# Schematic.net
KiCad netlist of a schematic drawn in EAGLE
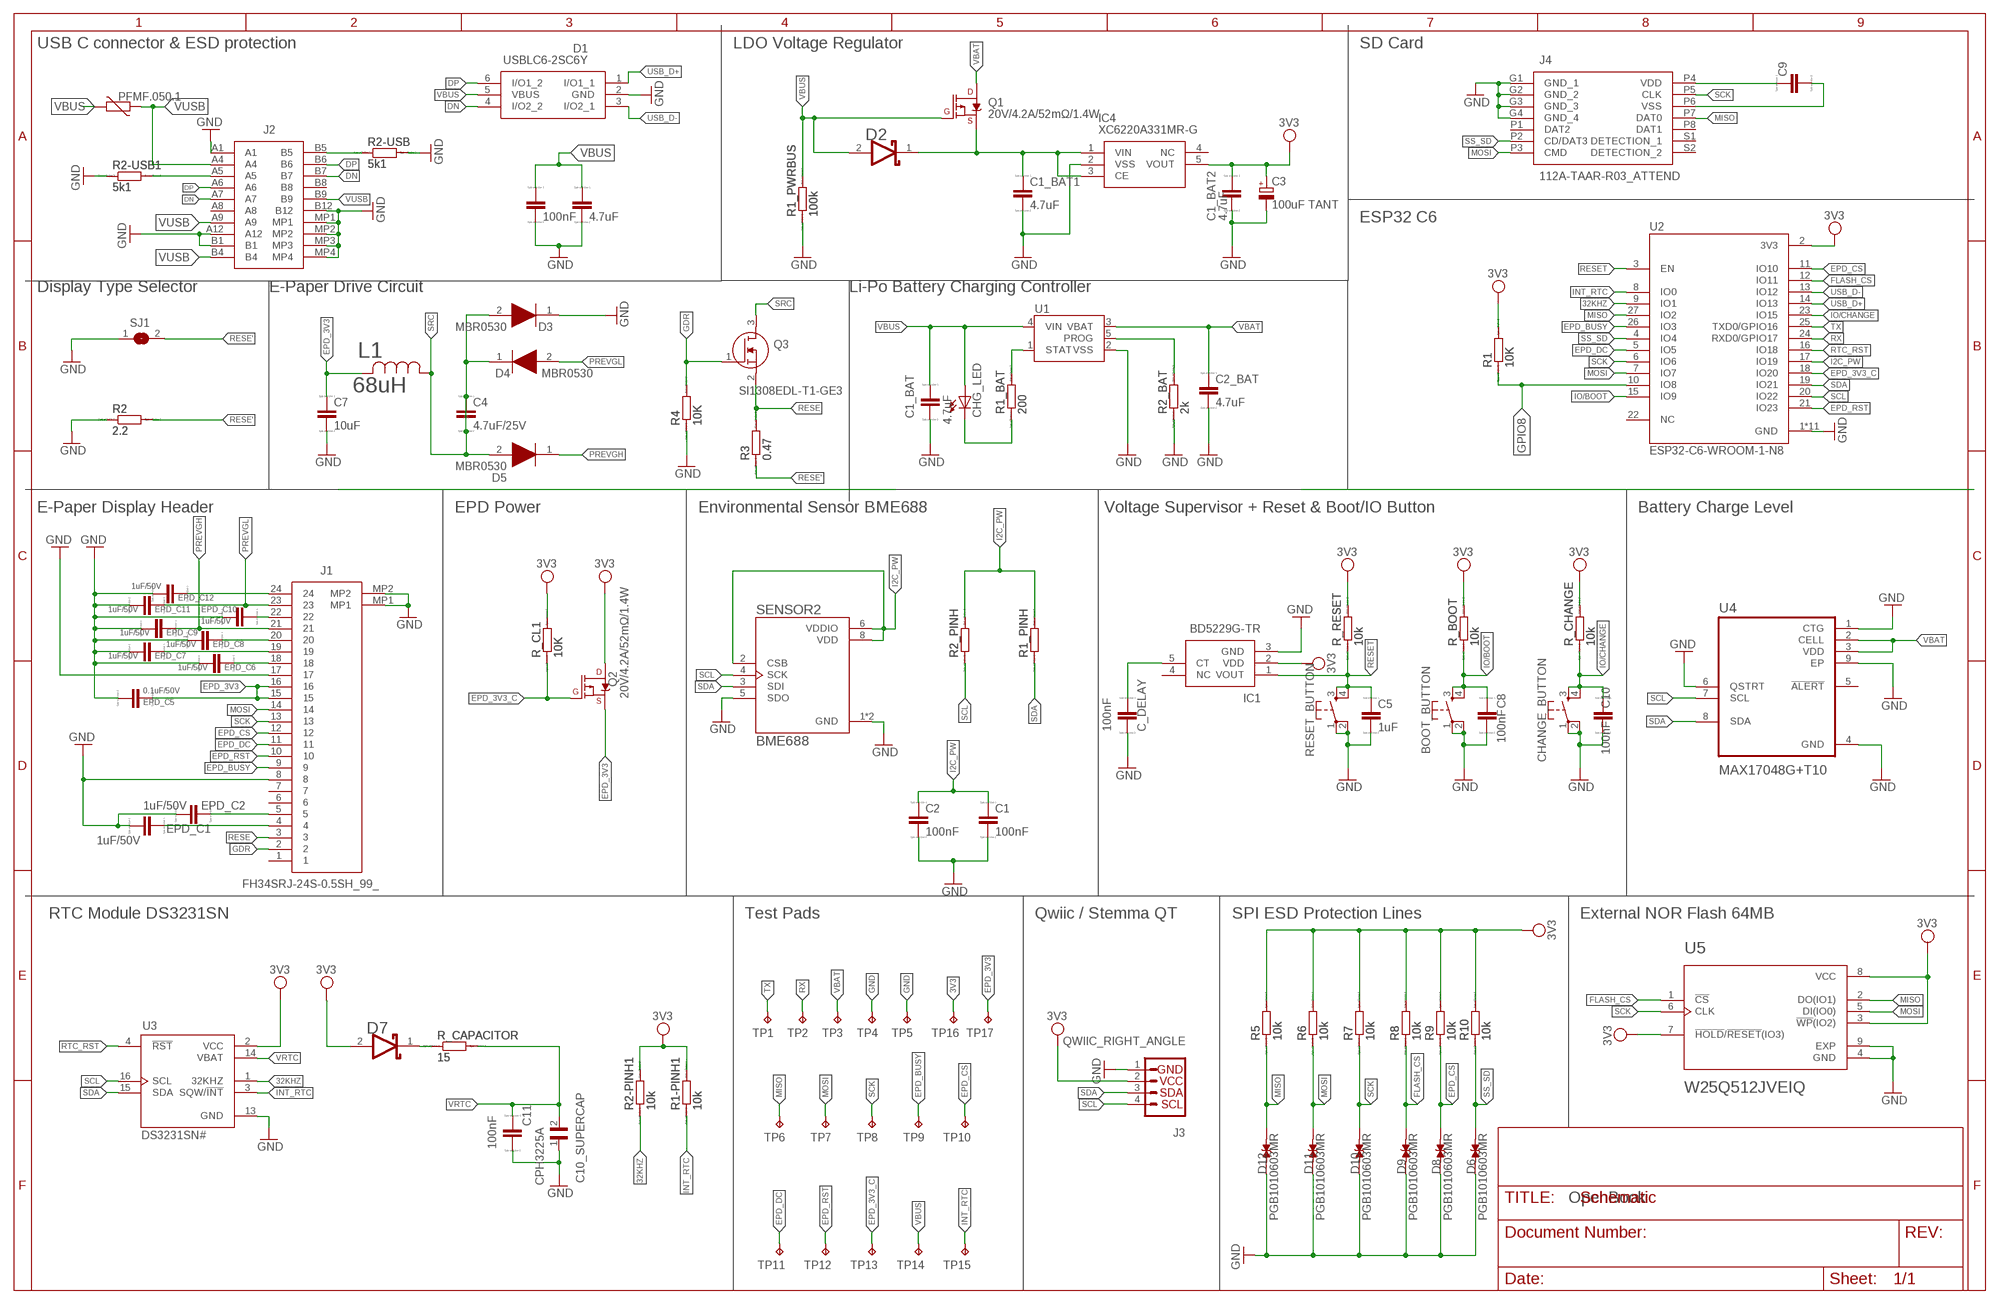
[diagram p0: schematic, sheet 1]

(export (version "E")
  (design (tool "Eeschema 10.0.6"))
  (components
    (comp (ref "BOOT_BUTTON")
      (value "BUTTON_CUSYOMV1")
      (footprint "eagle-import:MYBUTTON")
      (libsource (lib "eagle-import") (part "BUTTON_CUSYOMV1"))
    )
    (comp (ref "C1")
      (value "100nF")
      (footprint "eagle-import:ESP32_WROVER_EAGLE-LTSPICE_C0402")
      (libsource (lib "eagle-import") (part "ESP32_WROVER_EAGLE-LTSPICE_CC0402"))
    )
    (comp (ref "C1_BAT")
      (value "4.7uF")
      (footprint "eagle-import:EAGLE-LTSPICE_C0402")
      (libsource (lib "eagle-import") (part "EAGLE-LTSPICE_CC0402"))
    )
    (comp (ref "C1_BAT1")
      (value "4.7uF")
      (footprint "eagle-import:EAGLE-LTSPICE_C0402")
      (libsource (lib "eagle-import") (part "EAGLE-LTSPICE_CC0402"))
    )
    (comp (ref "C1_BAT2")
      (value "4.7uF")
      (footprint "eagle-import:EAGLE-LTSPICE_C0402")
      (libsource (lib "eagle-import") (part "EAGLE-LTSPICE_CC0402"))
    )
    (comp (ref "C2")
      (value "100nF")
      (footprint "eagle-import:ESP32_WROVER_EAGLE-LTSPICE_C0402")
      (libsource (lib "eagle-import") (part "ESP32_WROVER_EAGLE-LTSPICE_CC0402"))
    )
    (comp (ref "C2_BAT")
      (value "4.7uF")
      (footprint "eagle-import:EAGLE-LTSPICE_C0402")
      (libsource (lib "eagle-import") (part "EAGLE-LTSPICE_CC0402"))
    )
    (comp (ref "C3")
      (value "100uF TANT")
      (footprint "eagle-import:RCL_CT3528")
      (libsource (lib "eagle-import") (part "RCL_CPOL-EUCT3528"))
    )
    (comp (ref "C4")
      (value "4.7uF/25V")
      (footprint "eagle-import:EAGLE-LTSPICE_C0402")
      (libsource (lib "eagle-import") (part "EAGLE-LTSPICE_CC0402"))
    )
    (comp (ref "C4_USB")
      (value "100nF")
      (footprint "eagle-import:EAGLE-LTSPICE_C0402")
      (libsource (lib "eagle-import") (part "EAGLE-LTSPICE_CC0402"))
    )
    (comp (ref "C5")
      (value "1uF")
      (footprint "eagle-import:EAGLE-LTSPICE_C0402")
      (libsource (lib "eagle-import") (part "EAGLE-LTSPICE_CC0402"))
    )
    (comp (ref "C5_USB")
      (value "4.7uF")
      (footprint "eagle-import:EAGLE-LTSPICE_C0402")
      (libsource (lib "eagle-import") (part "EAGLE-LTSPICE_CC0402"))
    )
    (comp (ref "C7")
      (value "10uF")
      (footprint "eagle-import:EAGLE-LTSPICE_C0402")
      (libsource (lib "eagle-import") (part "EAGLE-LTSPICE_CC0402"))
    )
    (comp (ref "C8")
      (value "100nF")
      (footprint "eagle-import:EAGLE-LTSPICE_C0402")
      (libsource (lib "eagle-import") (part "EAGLE-LTSPICE_CC0402"))
    )
    (comp (ref "C9")
      (value "EAGLE-LTSPICE_CC0402")
      (footprint "eagle-import:EAGLE-LTSPICE_C0402")
      (libsource (lib "eagle-import") (part "EAGLE-LTSPICE_CC0402"))
    )
    (comp (ref "C10")
      (value "100nF")
      (footprint "eagle-import:EAGLE-LTSPICE_C0402")
      (libsource (lib "eagle-import") (part "EAGLE-LTSPICE_CC0402"))
    )
    (comp (ref "C10_SUPERCAP")
      (value "CPH3225A")
      (footprint "eagle-import:CAPCP3225X100N")
      (fields (field (name "MF") "Seiko Instruments"))
      (libsource (lib "eagle-import") (part "CPH3225A"))
    )
    (comp (ref "C11")
      (value "100nF")
      (footprint "eagle-import:EAGLE-LTSPICE_C0402")
      (libsource (lib "eagle-import") (part "EAGLE-LTSPICE_CC0402"))
    )
    (comp (ref "CHANGE_BUTTON")
      (value "BUTTON_CUSYOMV1")
      (footprint "eagle-import:MYBUTTON")
      (libsource (lib "eagle-import") (part "BUTTON_CUSYOMV1"))
    )
    (comp (ref "CHG_LED")
      (value "ADAFRUIT_LEDCHIP-LED0603")
      (footprint "eagle-import:ADAFRUIT_CHIP-LED0603")
      (libsource (lib "eagle-import") (part "ADAFRUIT_LEDCHIP-LED0603"))
    )
    (comp (ref "C_DELAY")
      (value "100nF")
      (footprint "eagle-import:EAGLE-LTSPICE_C0402")
      (libsource (lib "eagle-import") (part "EAGLE-LTSPICE_CC0402"))
    )
    (comp (ref "D1")
      (value "USBLC6-2SC6Y")
      (footprint "eagle-import:SOT95P280X145-6N")
      (fields (field (name "MF") "STMicroelectronics"))
      (libsource (lib "eagle-import") (part "USBLC6-2SC6Y"))
    )
    (comp (ref "D2")
      (value "ESP32_WROVER_AVX---SD0805S020S1R0_AVX_SD0805S020S1R0_0_0AVX_SD0805S020S1R0_0_0")
      (footprint "eagle-import:ESP32_WROVER_AVX---SD0805S020S1R0_AVX_SD0805S020S1R0_0")
      (fields
        (field (name "DIGIKEY_PART_NUMBER") "478-7800-1-ND")
        (field (name "MF") "AVX")
        (field (name "MOUSER_PART_NUMBER") "581-SD0805S020S1R0")
      )
      (libsource (lib "eagle-import") (part "ESP32_WROVER_AVX---SD0805S020S1R0_AVX_SD0805S020S1R0_0_0AVX_SD0805S020S1R0_0_0"))
    )
    (comp (ref "D3")
      (value "MBR0530")
      (footprint "eagle-import:SOD3716X135N")
      (fields (field (name "MF") "ON Semiconductor"))
      (libsource (lib "eagle-import") (part "MBR0530"))
    )
    (comp (ref "D4")
      (value "MBR0530")
      (footprint "eagle-import:SOD3716X135N")
      (fields (field (name "MF") "ON Semiconductor"))
      (libsource (lib "eagle-import") (part "MBR0530"))
    )
    (comp (ref "D5")
      (value "MBR0530")
      (footprint "eagle-import:SOD3716X135N")
      (fields (field (name "MF") "ON Semiconductor"))
      (libsource (lib "eagle-import") (part "MBR0530"))
    )
    (comp (ref "D6")
      (value "PGB1010603MR")
      (footprint "eagle-import:DIOC1608X36N")
      (fields (field (name "MF") "Littelfuse Inc."))
      (libsource (lib "eagle-import") (part "PGB1010603MR"))
    )
    (comp (ref "D7")
      (value "ESP32_WROVER_AVX---SD0805S020S1R0_AVX_SD0805S020S1R0_0_0AVX_SD0805S020S1R0_0_0")
      (footprint "eagle-import:ESP32_WROVER_AVX---SD0805S020S1R0_AVX_SD0805S020S1R0_0")
      (fields
        (field (name "DIGIKEY_PART_NUMBER") "478-7800-1-ND")
        (field (name "MF") "AVX")
        (field (name "MOUSER_PART_NUMBER") "581-SD0805S020S1R0")
      )
      (libsource (lib "eagle-import") (part "ESP32_WROVER_AVX---SD0805S020S1R0_AVX_SD0805S020S1R0_0_0AVX_SD0805S020S1R0_0_0"))
    )
    (comp (ref "D8")
      (value "PGB1010603MR")
      (footprint "eagle-import:DIOC1608X36N")
      (fields (field (name "MF") "Littelfuse Inc."))
      (libsource (lib "eagle-import") (part "PGB1010603MR"))
    )
    (comp (ref "D9")
      (value "PGB1010603MR")
      (footprint "eagle-import:DIOC1608X36N")
      (fields (field (name "MF") "Littelfuse Inc."))
      (libsource (lib "eagle-import") (part "PGB1010603MR"))
    )
    (comp (ref "D10")
      (value "PGB1010603MR")
      (footprint "eagle-import:DIOC1608X36N")
      (fields (field (name "MF") "Littelfuse Inc."))
      (libsource (lib "eagle-import") (part "PGB1010603MR"))
    )
    (comp (ref "D11")
      (value "PGB1010603MR")
      (footprint "eagle-import:DIOC1608X36N")
      (fields (field (name "MF") "Littelfuse Inc."))
      (libsource (lib "eagle-import") (part "PGB1010603MR"))
    )
    (comp (ref "D12")
      (value "PGB1010603MR")
      (footprint "eagle-import:DIOC1608X36N")
      (fields (field (name "MF") "Littelfuse Inc."))
      (libsource (lib "eagle-import") (part "PGB1010603MR"))
    )
    (comp (ref "EPD_C1")
      (value "1uF/50V")
      (footprint "eagle-import:EAGLE-LTSPICE_C0402")
      (libsource (lib "eagle-import") (part "EAGLE-LTSPICE_CC0402"))
    )
    (comp (ref "EPD_C2")
      (value "1uF/50V")
      (footprint "eagle-import:EAGLE-LTSPICE_C0402")
      (libsource (lib "eagle-import") (part "EAGLE-LTSPICE_CC0402"))
    )
    (comp (ref "EPD_C5")
      (value "0.1uF/50V")
      (footprint "eagle-import:EAGLE-LTSPICE_C0402")
      (libsource (lib "eagle-import") (part "EAGLE-LTSPICE_CC0402"))
    )
    (comp (ref "EPD_C6")
      (value "1uF/50V")
      (footprint "eagle-import:EAGLE-LTSPICE_C0402")
      (libsource (lib "eagle-import") (part "EAGLE-LTSPICE_CC0402"))
    )
    (comp (ref "EPD_C7")
      (value "1uF/50V")
      (footprint "eagle-import:EAGLE-LTSPICE_C0402")
      (libsource (lib "eagle-import") (part "EAGLE-LTSPICE_CC0402"))
    )
    (comp (ref "EPD_C8")
      (value "1uF/50V")
      (footprint "eagle-import:EAGLE-LTSPICE_C0402")
      (libsource (lib "eagle-import") (part "EAGLE-LTSPICE_CC0402"))
    )
    (comp (ref "EPD_C9")
      (value "1uF/50V")
      (footprint "eagle-import:EAGLE-LTSPICE_C0402")
      (libsource (lib "eagle-import") (part "EAGLE-LTSPICE_CC0402"))
    )
    (comp (ref "EPD_C10")
      (value "1uF/50V")
      (footprint "eagle-import:EAGLE-LTSPICE_C0402")
      (libsource (lib "eagle-import") (part "EAGLE-LTSPICE_CC0402"))
    )
    (comp (ref "EPD_C11")
      (value "1uF/50V")
      (footprint "eagle-import:EAGLE-LTSPICE_C0402")
      (libsource (lib "eagle-import") (part "EAGLE-LTSPICE_CC0402"))
    )
    (comp (ref "EPD_C12")
      (value "1uF/50V")
      (footprint "eagle-import:EAGLE-LTSPICE_C0402")
      (libsource (lib "eagle-import") (part "EAGLE-LTSPICE_CC0402"))
    )
    (comp (ref "IC1")
      (value "BD5229G-TR")
      (footprint "eagle-import:SOT95P280X125-5N")
      (fields (field (name "MOUSER_PART_NUMBER") "755-BD5229G-TR"))
      (libsource (lib "eagle-import") (part "BD5229G-TR"))
    )
    (comp (ref "IC4")
      (value "XC6220A331MR-G")
      (footprint "eagle-import:SOT95P280X120-5N")
      (fields (field (name "MOUSER_PART_NUMBER") "865-XC6220A331MR-G"))
      (libsource (lib "eagle-import") (part "XC6220A331MR-G"))
    )
    (comp (ref "J1")
      (value "FH34SRJ-24S-0.5SH_99_")
      (footprint "eagle-import:FH34SRJ24S05SH99")
      (fields
        (field (name "MANUFACTURER_PART_NUMBER") "FH34SRJ-24S-0.5SH(99)")
        (field (name "MOUSER_PART_NUMBER") "798-FH34SRJ24S05SH99")
      )
      (libsource (lib "eagle-import") (part "FH34SRJ-24S-0.5SH_99_"))
    )
    (comp (ref "J2")
      (value "SAMACSYS_PARTS_USB4110-GF-A")
      (footprint "eagle-import:SAMACSYS_PARTS_USB4110GFA")
      (fields
        (field (name "MANUFACTURER_PART_NUMBER") "USB4110-GF-A")
        (field (name "MOUSER_PART_NUMBER") "640-USB4110-GF-A")
      )
      (libsource (lib "eagle-import") (part "SAMACSYS_PARTS_USB4110-GF-A"))
    )
    (comp (ref "J3")
      (value "QWIIC_RIGHT_ANGLE")
      (footprint "eagle-import:JST04_1MM_RA")
      (libsource (lib "eagle-import") (part "QWIIC_CONNECTORJS-1MM"))
    )
    (comp (ref "J4")
      (value "112A-TAAR-R03_ATTEND")
      (footprint "eagle-import:112ATAARR03ATTEND")
      (fields (field (name "MANUFACTURER_PART_NUMBER") "112A-TAAR-R03 ATTEND"))
      (libsource (lib "eagle-import") (part "112A-TAAR-R03_ATTEND"))
    )
    (comp (ref "L1")
      (value "68uH")
      (footprint "eagle-import:IND_4828-WE-TPC_WRE")
      (fields
        (field (name "MANUFACTURER_PART_NUMBER") "744043680")
        (field (name "COPYRIGHT") "Copyright (C) 2024 Ultra Librarian. All rights reserved.")
      )
      (libsource (lib "eagle-import") (part "744043680IND_4828-WE-TPC_WRE"))
    )
    (comp (ref "PFMF.050.1")
      (value "ESP32C6_VARISTORCN1812")
      (footprint "eagle-import:ESP32C6_VARISTOR_CT_CN1812")
      (libsource (lib "eagle-import") (part "ESP32C6_VARISTORCN1812"))
    )
    (comp (ref "Q1")
      (value "20V/4.2A/52mΩ/1.4W")
      (footprint "eagle-import:ESP32_WROVER_SPARKFUN-DISCRETESEMI_SOT23-3")
      (libsource (lib "eagle-import") (part "ESP32_WROVER_SPARKFUN-DISCRETESEMI_MOSFET_PCH-DMG2305UX-7"))
    )
    (comp (ref "Q2")
      (value "20V/4.2A/52mΩ/1.4W")
      (footprint "eagle-import:ESP32_WROVER_SPARKFUN-DISCRETESEMI_SOT23-3")
      (libsource (lib "eagle-import") (part "ESP32_WROVER_SPARKFUN-DISCRETESEMI_MOSFET_PCH-DMG2305UX-7"))
    )
    (comp (ref "Q3")
      (value "SI1308EDL-T1-GE3")
      (footprint "eagle-import:SOT65P210X110-3N")
      (fields (field (name "MF") "Vishay Siliconix"))
      (libsource (lib "eagle-import") (part "SI1308EDL-T1-GE3"))
    )
    (comp (ref "R1")
      (value "10K")
      (footprint "eagle-import:ESP32_WROVER_EAGLE-LTSPICE_R0402")
      (libsource (lib "eagle-import") (part "ESP32_WROVER_EAGLE-LTSPICE_RR0402"))
    )
    (comp (ref "R1-PINH1")
      (value "10k")
      (footprint "eagle-import:ESP32_WROVER_EAGLE-LTSPICE_R0402")
      (libsource (lib "eagle-import") (part "ESP32_WROVER_EAGLE-LTSPICE_RR0402"))
    )
    (comp (ref "R1_BAT")
      (value "200")
      (footprint "eagle-import:ESP32_WROVER_EAGLE-LTSPICE_R0402")
      (libsource (lib "eagle-import") (part "ESP32_WROVER_EAGLE-LTSPICE_RR0402"))
    )
    (comp (ref "R1_PINH")
      (value "ESP32_WROVER_EAGLE-LTSPICE_RR0402")
      (footprint "eagle-import:ESP32_WROVER_EAGLE-LTSPICE_R0402")
      (libsource (lib "eagle-import") (part "ESP32_WROVER_EAGLE-LTSPICE_RR0402"))
    )
    (comp (ref "R1_PWRBUS")
      (value "100k")
      (footprint "eagle-import:ESP32_WROVER_EAGLE-LTSPICE_R0402")
      (libsource (lib "eagle-import") (part "ESP32_WROVER_EAGLE-LTSPICE_RR0402"))
    )
    (comp (ref "R2")
      (value "2.2")
      (footprint "eagle-import:ESP32_WROVER_EAGLE-LTSPICE_R0402")
      (libsource (lib "eagle-import") (part "ESP32_WROVER_EAGLE-LTSPICE_RR0402"))
    )
    (comp (ref "R2-PINH1")
      (value "10k")
      (footprint "eagle-import:ESP32_WROVER_EAGLE-LTSPICE_R0402")
      (libsource (lib "eagle-import") (part "ESP32_WROVER_EAGLE-LTSPICE_RR0402"))
    )
    (comp (ref "R2-USB")
      (value "5k1")
      (footprint "eagle-import:ESP32_WROVER_EAGLE-LTSPICE_R0402")
      (libsource (lib "eagle-import") (part "ESP32_WROVER_EAGLE-LTSPICE_RR0402"))
    )
    (comp (ref "R2-USB1")
      (value "5k1")
      (footprint "eagle-import:ESP32_WROVER_EAGLE-LTSPICE_R0402")
      (libsource (lib "eagle-import") (part "ESP32_WROVER_EAGLE-LTSPICE_RR0402"))
    )
    (comp (ref "R2_BAT")
      (value "2k")
      (footprint "eagle-import:ESP32_WROVER_EAGLE-LTSPICE_R0402")
      (libsource (lib "eagle-import") (part "ESP32_WROVER_EAGLE-LTSPICE_RR0402"))
    )
    (comp (ref "R2_PINH")
      (value "ESP32_WROVER_EAGLE-LTSPICE_RR0402")
      (footprint "eagle-import:ESP32_WROVER_EAGLE-LTSPICE_R0402")
      (libsource (lib "eagle-import") (part "ESP32_WROVER_EAGLE-LTSPICE_RR0402"))
    )
    (comp (ref "R3")
      (value "0.47")
      (footprint "eagle-import:ESP32_WROVER_EAGLE-LTSPICE_R0402")
      (libsource (lib "eagle-import") (part "ESP32_WROVER_EAGLE-LTSPICE_RR0402"))
    )
    (comp (ref "R4")
      (value "10K")
      (footprint "eagle-import:ESP32_WROVER_EAGLE-LTSPICE_R0402")
      (libsource (lib "eagle-import") (part "ESP32_WROVER_EAGLE-LTSPICE_RR0402"))
    )
    (comp (ref "R5")
      (value "10k")
      (footprint "eagle-import:ESP32_WROVER_EAGLE-LTSPICE_R0402")
      (libsource (lib "eagle-import") (part "ESP32_WROVER_EAGLE-LTSPICE_RR0402"))
    )
    (comp (ref "R6")
      (value "10k")
      (footprint "eagle-import:ESP32_WROVER_EAGLE-LTSPICE_R0402")
      (libsource (lib "eagle-import") (part "ESP32_WROVER_EAGLE-LTSPICE_RR0402"))
    )
    (comp (ref "R7")
      (value "10k")
      (footprint "eagle-import:ESP32_WROVER_EAGLE-LTSPICE_R0402")
      (libsource (lib "eagle-import") (part "ESP32_WROVER_EAGLE-LTSPICE_RR0402"))
    )
    (comp (ref "R8")
      (value "10k")
      (footprint "eagle-import:ESP32_WROVER_EAGLE-LTSPICE_R0402")
      (libsource (lib "eagle-import") (part "ESP32_WROVER_EAGLE-LTSPICE_RR0402"))
    )
    (comp (ref "R9")
      (value "10k")
      (footprint "eagle-import:ESP32_WROVER_EAGLE-LTSPICE_R0402")
      (libsource (lib "eagle-import") (part "ESP32_WROVER_EAGLE-LTSPICE_RR0402"))
    )
    (comp (ref "R10")
      (value "10k")
      (footprint "eagle-import:ESP32_WROVER_EAGLE-LTSPICE_R0402")
      (libsource (lib "eagle-import") (part "ESP32_WROVER_EAGLE-LTSPICE_RR0402"))
    )
    (comp (ref "RESET_BUTTON")
      (value "BUTTON_CUSYOMV1")
      (footprint "eagle-import:MYBUTTON")
      (libsource (lib "eagle-import") (part "BUTTON_CUSYOMV1"))
    )
    (comp (ref "R_BOOT")
      (value "10k")
      (footprint "eagle-import:ESP32_WROVER_EAGLE-LTSPICE_R0402")
      (libsource (lib "eagle-import") (part "ESP32_WROVER_EAGLE-LTSPICE_RR0402"))
    )
    (comp (ref "R_CAPACITOR")
      (value "15")
      (footprint "eagle-import:ESP32_WROVER_EAGLE-LTSPICE_R0402")
      (libsource (lib "eagle-import") (part "ESP32_WROVER_EAGLE-LTSPICE_RR0402"))
    )
    (comp (ref "R_CHANGE")
      (value "10k")
      (footprint "eagle-import:ESP32_WROVER_EAGLE-LTSPICE_R0402")
      (libsource (lib "eagle-import") (part "ESP32_WROVER_EAGLE-LTSPICE_RR0402"))
    )
    (comp (ref "R_CL1")
      (value "10K")
      (footprint "eagle-import:ESP32_WROVER_EAGLE-LTSPICE_R0402")
      (libsource (lib "eagle-import") (part "ESP32_WROVER_EAGLE-LTSPICE_RR0402"))
    )
    (comp (ref "R_RESET")
      (value "10k")
      (footprint "eagle-import:ESP32_WROVER_EAGLE-LTSPICE_R0402")
      (libsource (lib "eagle-import") (part "ESP32_WROVER_EAGLE-LTSPICE_RR0402"))
    )
    (comp (ref "SENSOR2")
      (value "BME688")
      (footprint "eagle-import:ESP32_WROVER_BME680_PSON80P300X300X100-8N")
      (fields (field (name "MF") "Bosch Sensortec") (field (name "MP") "BME680"))
      (libsource (lib "eagle-import") (part "ESP32_WROVER_BME680_BME680"))
    )
    (comp (ref "SJ1") (value "SJ") (footprint "eagle-import:SJ") (libsource (lib "eagle-import") (part "SJ")))
    (comp (ref "TP1")
      (value "TPTP20R")
      (footprint "eagle-import:TP20R")
      (libsource (lib "eagle-import") (part "TPTP20R"))
    )
    (comp (ref "TP2")
      (value "TPTP20R")
      (footprint "eagle-import:TP20R")
      (libsource (lib "eagle-import") (part "TPTP20R"))
    )
    (comp (ref "TP3")
      (value "TPTP20R")
      (footprint "eagle-import:TP20R")
      (libsource (lib "eagle-import") (part "TPTP20R"))
    )
    (comp (ref "TP4")
      (value "TPTP20R")
      (footprint "eagle-import:TP20R")
      (libsource (lib "eagle-import") (part "TPTP20R"))
    )
    (comp (ref "TP5")
      (value "TPTP20R")
      (footprint "eagle-import:TP20R")
      (libsource (lib "eagle-import") (part "TPTP20R"))
    )
    (comp (ref "TP6")
      (value "TPTP20R")
      (footprint "eagle-import:TP20R")
      (libsource (lib "eagle-import") (part "TPTP20R"))
    )
    (comp (ref "TP7")
      (value "TPTP20R")
      (footprint "eagle-import:TP20R")
      (libsource (lib "eagle-import") (part "TPTP20R"))
    )
    (comp (ref "TP8")
      (value "TPTP20R")
      (footprint "eagle-import:TP20R")
      (libsource (lib "eagle-import") (part "TPTP20R"))
    )
    (comp (ref "TP9")
      (value "TPTP20R")
      (footprint "eagle-import:TP20R")
      (libsource (lib "eagle-import") (part "TPTP20R"))
    )
    (comp (ref "TP10")
      (value "TPTP20R")
      (footprint "eagle-import:TP20R")
      (libsource (lib "eagle-import") (part "TPTP20R"))
    )
    (comp (ref "TP11")
      (value "TPTP20R")
      (footprint "eagle-import:TP20R")
      (libsource (lib "eagle-import") (part "TPTP20R"))
    )
    (comp (ref "TP12")
      (value "TPTP20R")
      (footprint "eagle-import:TP20R")
      (libsource (lib "eagle-import") (part "TPTP20R"))
    )
    (comp (ref "TP13")
      (value "TPTP20R")
      (footprint "eagle-import:TP20R")
      (libsource (lib "eagle-import") (part "TPTP20R"))
    )
    (comp (ref "TP14")
      (value "TPTP20R")
      (footprint "eagle-import:TP20R")
      (libsource (lib "eagle-import") (part "TPTP20R"))
    )
    (comp (ref "TP15")
      (value "TPTP20R")
      (footprint "eagle-import:TP20R")
      (libsource (lib "eagle-import") (part "TPTP20R"))
    )
    (comp (ref "TP16")
      (value "TPTP20R")
      (footprint "eagle-import:TP20R")
      (libsource (lib "eagle-import") (part "TPTP20R"))
    )
    (comp (ref "TP17")
      (value "TPTP20R")
      (footprint "eagle-import:TP20R")
      (libsource (lib "eagle-import") (part "TPTP20R"))
    )
    (comp (ref "U1")
      (value "ESP32_WROVER_SPARKFUN-IC-POWER_MCP73831")
      (footprint "eagle-import:ESP32_WROVER_SPARKFUN-IC-POWER_SOT23-5")
      (libsource (lib "eagle-import") (part "ESP32_WROVER_SPARKFUN-IC-POWER_MCP73831"))
    )
    (comp (ref "U2")
      (value "ESP32-C6-WROOM-1-N8")
      (footprint "eagle-import:XCVR_ESP32-C6-WROOM-1-N8")
      (fields (field (name "MF") "Espressif Systems"))
      (libsource (lib "eagle-import") (part "ESP32-C6-WROOM-1-N8"))
    )
    (comp (ref "U3")
      (value "DS3231SN#")
      (footprint "eagle-import:SOIC127P1032X265-16N")
      (fields (field (name "MF") "Analog Devices"))
      (libsource (lib "eagle-import") (part "DS3231SN#"))
    )
    (comp (ref "U4")
      (value "MAX17048G+T10")
      (footprint "eagle-import:SON50P200X200X80-9N")
      (fields (field (name "MF") "Analog Devices"))
      (libsource (lib "eagle-import") (part "MAX17048G+T10"))
    )
    (comp (ref "U5")
      (value "W25Q512JVEIQ")
      (footprint "eagle-import:SON127P600X800X80-9N")
      (fields (field (name "MF") "Winbond Electronics"))
      (libsource (lib "eagle-import") (part "W25Q512JVEIQ"))
    )
  )
  (nets
    (net (code "1") (name "3V3") (class "Default")
      (node (ref "C1_BAT2") (pin "1") (pinfunction "1_1") (pintype "passive"))
      (node (ref "C3") (pin "+") (pinfunction "+_+") (pintype "passive"))
      (node (ref "D7") (pin "2") (pinfunction "ANODE_2") (pintype "bidirectional"))
      (node (ref "IC1") (pin "2") (pinfunction "VDD_2") (pintype "bidirectional"))
      (node (ref "IC4") (pin "5") (pinfunction "VOUT_5") (pintype "bidirectional"))
      (node (ref "J3") (pin "2") (pinfunction "2_2") (pintype "power_in"))
      (node (ref "Q2") (pin "3") (pinfunction "D_3") (pintype "bidirectional"))
      (node (ref "R1") (pin "2") (pinfunction "2_2") (pintype "passive"))
      (node (ref "R1-PINH1") (pin "2") (pinfunction "2_2") (pintype "passive"))
      (node (ref "R10") (pin "2") (pinfunction "2_2") (pintype "passive"))
      (node (ref "R2-PINH1") (pin "2") (pinfunction "2_2") (pintype "passive"))
      (node (ref "R5") (pin "2") (pinfunction "2_2") (pintype "passive"))
      (node (ref "R6") (pin "2") (pinfunction "2_2") (pintype "passive"))
      (node (ref "R7") (pin "2") (pinfunction "2_2") (pintype "passive"))
      (node (ref "R8") (pin "2") (pinfunction "2_2") (pintype "passive"))
      (node (ref "R9") (pin "2") (pinfunction "2_2") (pintype "passive"))
      (node (ref "R_BOOT") (pin "2") (pinfunction "2_2") (pintype "passive"))
      (node (ref "R_CHANGE") (pin "2") (pinfunction "2_2") (pintype "passive"))
      (node (ref "R_CL1") (pin "2") (pinfunction "2_2") (pintype "passive"))
      (node (ref "R_RESET") (pin "2") (pinfunction "2_2") (pintype "passive"))
      (node (ref "TP16") (pin "TP") (pinfunction "TP_TP") (pintype "input"))
      (node (ref "U2") (pin "2") (pinfunction "3V3_2") (pintype "power_in"))
      (node (ref "U3") (pin "2") (pinfunction "VCC_2") (pintype "power_in"))
      (node (ref "U5") (pin "3") (pinfunction "~{WP}(IO2)_3") (pintype "bidirectional"))
      (node (ref "U5") (pin "7") (pinfunction "~{HOLD}/~{RESET}(IO3)_7") (pintype "bidirectional"))
      (node (ref "U5") (pin "8") (pinfunction "VCC_8") (pintype "power_in"))
    )
    (net (code "2") (name "32KHZ") (class "Default")
      (node (ref "R2-PINH1") (pin "1") (pinfunction "1_1") (pintype "passive"))
      (node (ref "U2") (pin "9") (pinfunction "IO1_9") (pintype "bidirectional"))
      (node (ref "U3") (pin "1") (pinfunction "32KHZ_1") (pintype "output"))
    )
    (net (code "3") (name "DN") (class "Default")
      (node (ref "D1") (pin "4") (pinfunction "I/O2_2_4") (pintype "bidirectional"))
      (node (ref "J2") (pin "A7") (pinfunction "A7_A7") (pintype "bidirectional"))
      (node (ref "J2") (pin "B7") (pinfunction "B7_B7") (pintype "bidirectional"))
    )
    (net (code "4") (name "DP") (class "Default")
      (node (ref "D1") (pin "6") (pinfunction "I/O1_2_6") (pintype "bidirectional"))
      (node (ref "J2") (pin "A6") (pinfunction "A6_A6") (pintype "bidirectional"))
      (node (ref "J2") (pin "B6") (pinfunction "B6_B6") (pintype "bidirectional"))
    )
    (net (code "5") (name "EPD_3V3") (class "Default")
      (node (ref "C7") (pin "1") (pinfunction "1_1") (pintype "passive"))
      (node (ref "EPD_C5") (pin "1") (pinfunction "1_1") (pintype "passive"))
      (node (ref "J1") (pin "15") (pinfunction "15_15") (pintype "bidirectional"))
      (node (ref "J1") (pin "16") (pinfunction "16_16") (pintype "bidirectional"))
      (node (ref "L1") (pin "2") (pinfunction "2_2") (pintype "passive"))
      (node (ref "Q2") (pin "2") (pinfunction "S_2") (pintype "bidirectional"))
      (node (ref "TP17") (pin "TP") (pinfunction "TP_TP") (pintype "input"))
    )
    (net (code "6") (name "EPD_3V3_C") (class "Default")
      (node (ref "Q2") (pin "1") (pinfunction "G_1") (pintype "bidirectional"))
      (node (ref "R_CL1") (pin "1") (pinfunction "1_1") (pintype "passive"))
      (node (ref "TP13") (pin "TP") (pinfunction "TP_TP") (pintype "input"))
      (node (ref "U2") (pin "18") (pinfunction "IO20_18") (pintype "bidirectional"))
    )
    (net (code "7") (name "EPD_BUSY") (class "Default")
      (node (ref "J1") (pin "9") (pinfunction "9_9") (pintype "bidirectional"))
      (node (ref "TP9") (pin "TP") (pinfunction "TP_TP") (pintype "input"))
      (node (ref "U2") (pin "26") (pinfunction "IO3_26") (pintype "bidirectional"))
    )
    (net (code "8") (name "EPD_CS") (class "Default")
      (node (ref "D8") (pin "2") (pinfunction "2_2") (pintype "passive"))
      (node (ref "J1") (pin "12") (pinfunction "12_12") (pintype "bidirectional"))
      (node (ref "R9") (pin "1") (pinfunction "1_1") (pintype "passive"))
      (node (ref "TP10") (pin "TP") (pinfunction "TP_TP") (pintype "input"))
      (node (ref "U2") (pin "11") (pinfunction "IO10_11") (pintype "bidirectional"))
    )
    (net (code "9") (name "EPD_DC") (class "Default")
      (node (ref "J1") (pin "11") (pinfunction "11_11") (pintype "bidirectional"))
      (node (ref "TP11") (pin "TP") (pinfunction "TP_TP") (pintype "input"))
      (node (ref "U2") (pin "5") (pinfunction "IO5_5") (pintype "bidirectional"))
    )
    (net (code "10") (name "EPD_RST") (class "Default")
      (node (ref "J1") (pin "10") (pinfunction "10_10") (pintype "bidirectional"))
      (node (ref "TP12") (pin "TP") (pinfunction "TP_TP") (pintype "input"))
      (node (ref "U2") (pin "21") (pinfunction "IO23_21") (pintype "bidirectional"))
    )
    (net (code "11") (name "FLASH_CS") (class "Default")
      (node (ref "D9") (pin "2") (pinfunction "2_2") (pintype "passive"))
      (node (ref "R8") (pin "1") (pinfunction "1_1") (pintype "passive"))
      (node (ref "U2") (pin "12") (pinfunction "IO11_12") (pintype "bidirectional"))
      (node (ref "U5") (pin "1") (pinfunction "~{CS}_1") (pintype "input"))
    )
    (net (code "12") (name "GDR") (class "Default")
      (node (ref "J1") (pin "2") (pinfunction "2_2") (pintype "bidirectional"))
      (node (ref "Q3") (pin "1") (pinfunction "G_1") (pintype "bidirectional"))
      (node (ref "R4") (pin "2") (pinfunction "2_2") (pintype "passive"))
    )
    (net (code "13") (name "GND") (class "Default")
      (node (ref "BOOT_BUTTON") (pin "1") (pinfunction "1_1") (pintype "passive"))
      (node (ref "BOOT_BUTTON") (pin "2") (pinfunction "2_2") (pintype "passive"))
      (node (ref "C1") (pin "2") (pinfunction "2_2") (pintype "passive"))
      (node (ref "C10") (pin "2") (pinfunction "2_2") (pintype "passive"))
      (node (ref "C10_SUPERCAP") (pin "1") (pinfunction "1_1") (pintype "passive"))
      (node (ref "C11") (pin "2") (pinfunction "2_2") (pintype "passive"))
      (node (ref "C1_BAT") (pin "2") (pinfunction "2_2") (pintype "passive"))
      (node (ref "C1_BAT1") (pin "2") (pinfunction "2_2") (pintype "passive"))
      (node (ref "C1_BAT2") (pin "2") (pinfunction "2_2") (pintype "passive"))
      (node (ref "C2") (pin "2") (pinfunction "2_2") (pintype "passive"))
      (node (ref "C2_BAT") (pin "2") (pinfunction "2_2") (pintype "passive"))
      (node (ref "C3") (pin "-") (pinfunction "-_-") (pintype "passive"))
      (node (ref "C4_USB") (pin "2") (pinfunction "2_2") (pintype "passive"))
      (node (ref "C5") (pin "2") (pinfunction "2_2") (pintype "passive"))
      (node (ref "C5_USB") (pin "2") (pinfunction "2_2") (pintype "passive"))
      (node (ref "C7") (pin "2") (pinfunction "2_2") (pintype "passive"))
      (node (ref "C8") (pin "2") (pinfunction "2_2") (pintype "passive"))
      (node (ref "CHANGE_BUTTON") (pin "1") (pinfunction "1_1") (pintype "passive"))
      (node (ref "CHANGE_BUTTON") (pin "2") (pinfunction "2_2") (pintype "passive"))
      (node (ref "C_DELAY") (pin "2") (pinfunction "2_2") (pintype "passive"))
      (node (ref "D1") (pin "2") (pinfunction "GND_2") (pintype "bidirectional"))
      (node (ref "D10") (pin "1") (pinfunction "1_1") (pintype "passive"))
      (node (ref "D11") (pin "1") (pinfunction "1_1") (pintype "passive"))
      (node (ref "D12") (pin "1") (pinfunction "1_1") (pintype "passive"))
      (node (ref "D3") (pin "1") (pinfunction "K_1") (pintype "bidirectional"))
      (node (ref "D6") (pin "1") (pinfunction "1_1") (pintype "passive"))
      (node (ref "D8") (pin "1") (pinfunction "1_1") (pintype "passive"))
      (node (ref "D9") (pin "1") (pinfunction "1_1") (pintype "passive"))
      (node (ref "EPD_C1") (pin "2") (pinfunction "2_2") (pintype "passive"))
      (node (ref "EPD_C10") (pin "2") (pinfunction "2_2") (pintype "passive"))
      (node (ref "EPD_C11") (pin "2") (pinfunction "2_2") (pintype "passive"))
      (node (ref "EPD_C12") (pin "2") (pinfunction "2_2") (pintype "passive"))
      (node (ref "EPD_C2") (pin "2") (pinfunction "2_2") (pintype "passive"))
      (node (ref "EPD_C5") (pin "2") (pinfunction "2_2") (pintype "passive"))
      (node (ref "EPD_C6") (pin "2") (pinfunction "2_2") (pintype "passive"))
      (node (ref "EPD_C7") (pin "2") (pinfunction "2_2") (pintype "passive"))
      (node (ref "EPD_C8") (pin "2") (pinfunction "2_2") (pintype "passive"))
      (node (ref "EPD_C9") (pin "2") (pinfunction "2_2") (pintype "passive"))
      (node (ref "IC1") (pin "3") (pinfunction "GND_3") (pintype "bidirectional"))
      (node (ref "IC4") (pin "2") (pinfunction "VSS_2") (pintype "bidirectional"))
      (node (ref "J1") (pin "17") (pinfunction "17_17") (pintype "bidirectional"))
      (node (ref "J1") (pin "8") (pinfunction "8_8") (pintype "bidirectional"))
      (node (ref "J1") (pin "MP1") (pinfunction "MP1_MP1") (pintype "bidirectional"))
      (node (ref "J1") (pin "MP2") (pinfunction "MP2_MP2") (pintype "bidirectional"))
      (node (ref "J2") (pin "A1") (pinfunction "A1_A1") (pintype "bidirectional"))
      (node (ref "J2") (pin "A12") (pinfunction "A12_A12") (pintype "bidirectional"))
      (node (ref "J2") (pin "B1") (pinfunction "B1_B1") (pintype "bidirectional"))
      (node (ref "J2") (pin "B12") (pinfunction "B12_B12") (pintype "bidirectional"))
      (node (ref "J2") (pin "MP1") (pinfunction "MP1_MP1") (pintype "bidirectional"))
      (node (ref "J2") (pin "MP2") (pinfunction "MP2_MP2") (pintype "bidirectional"))
      (node (ref "J2") (pin "MP3") (pinfunction "MP3_MP3") (pintype "bidirectional"))
      (node (ref "J2") (pin "MP4") (pinfunction "MP4_MP4") (pintype "bidirectional"))
      (node (ref "J3") (pin "1") (pinfunction "1_1") (pintype "power_in"))
      (node (ref "J4") (pin "G1") (pinfunction "GND_1_G1") (pintype "bidirectional"))
      (node (ref "J4") (pin "G2") (pinfunction "GND_2_G2") (pintype "bidirectional"))
      (node (ref "J4") (pin "G3") (pinfunction "GND_3_G3") (pintype "bidirectional"))
      (node (ref "J4") (pin "G4") (pinfunction "GND_4_G4") (pintype "bidirectional"))
      (node (ref "R1_PWRBUS") (pin "1") (pinfunction "1_1") (pintype "passive"))
      (node (ref "R2") (pin "1") (pinfunction "1_1") (pintype "passive"))
      (node (ref "R2-USB") (pin "2") (pinfunction "2_2") (pintype "passive"))
      (node (ref "R2-USB1") (pin "1") (pinfunction "1_1") (pintype "passive"))
      (node (ref "R2_BAT") (pin "1") (pinfunction "1_1") (pintype "passive"))
      (node (ref "R4") (pin "1") (pinfunction "1_1") (pintype "passive"))
      (node (ref "RESET_BUTTON") (pin "1") (pinfunction "1_1") (pintype "passive"))
      (node (ref "RESET_BUTTON") (pin "2") (pinfunction "2_2") (pintype "passive"))
      (node (ref "SENSOR2") (pin "1") (pinfunction "GND_1") (pintype "power_in"))
      (node (ref "SENSOR2") (pin "5") (pinfunction "SDO_5") (pintype "bidirectional"))
      (node (ref "SENSOR2") (pin "7") (pinfunction "GND_7") (pintype "power_in"))
      (node (ref "SJ1") (pin "1") (pinfunction "1_1") (pintype "passive"))
      (node (ref "TP4") (pin "TP") (pinfunction "TP_TP") (pintype "input"))
      (node (ref "TP5") (pin "TP") (pinfunction "TP_TP") (pintype "input"))
      (node (ref "U1") (pin "2") (pinfunction "VSS_2") (pintype "power_in"))
      (node (ref "U2") (pin "1") (pinfunction "GND_1") (pintype "power_in"))
      (node (ref "U2") (pin "28") (pinfunction "GND_28") (pintype "power_in"))
      (node (ref "U2") (pin "29_1") (pinfunction "GND_29_1") (pintype "power_in"))
      (node (ref "U2") (pin "29_2") (pinfunction "GND_29_2") (pintype "power_in"))
      (node (ref "U2") (pin "29_3") (pinfunction "GND_29_3") (pintype "power_in"))
      (node (ref "U2") (pin "29_4") (pinfunction "GND_29_4") (pintype "power_in"))
      (node (ref "U2") (pin "29_5") (pinfunction "GND_29_5") (pintype "power_in"))
      (node (ref "U2") (pin "29_6") (pinfunction "GND_29_6") (pintype "power_in"))
      (node (ref "U2") (pin "29_7") (pinfunction "GND_29_7") (pintype "power_in"))
      (node (ref "U2") (pin "29_8") (pinfunction "GND_29_8") (pintype "power_in"))
      (node (ref "U2") (pin "29_9") (pinfunction "GND_29_9") (pintype "power_in"))
      (node (ref "U3") (pin "13") (pinfunction "GND_13") (pintype "power_in"))
      (node (ref "U4") (pin "1") (pinfunction "CTG_1") (pintype "power_in"))
      (node (ref "U4") (pin "4") (pinfunction "GND_4") (pintype "power_in"))
      (node (ref "U4") (pin "6") (pinfunction "QSTRT_6") (pintype "input"))
      (node (ref "U4") (pin "9") (pinfunction "EP_9") (pintype "power_in"))
      (node (ref "U5") (pin "4") (pinfunction "GND_4") (pintype "power_in"))
      (node (ref "U5") (pin "9") (pinfunction "EXP_9") (pintype "passive"))
    )
    (net (code "14") (name "GPIO8") (class "Default")
      (node (ref "R1") (pin "1") (pinfunction "1_1") (pintype "passive"))
      (node (ref "U2") (pin "10") (pinfunction "IO8_10") (pintype "bidirectional"))
    )
    (net (code "15") (name "I2C_PW") (class "Default")
      (node (ref "C1") (pin "1") (pinfunction "1_1") (pintype "passive"))
      (node (ref "C2") (pin "1") (pinfunction "1_1") (pintype "passive"))
      (node (ref "R1_PINH") (pin "2") (pinfunction "2_2") (pintype "passive"))
      (node (ref "R2_PINH") (pin "2") (pinfunction "2_2") (pintype "passive"))
      (node (ref "SENSOR2") (pin "2") (pinfunction "CSB_2") (pintype "input"))
      (node (ref "SENSOR2") (pin "6") (pinfunction "VDDIO_6") (pintype "power_in"))
      (node (ref "SENSOR2") (pin "8") (pinfunction "VDD_8") (pintype "power_in"))
      (node (ref "U2") (pin "17") (pinfunction "IO19_17") (pintype "bidirectional"))
    )
    (net (code "16") (name "INT_RTC") (class "Default")
      (node (ref "R1-PINH1") (pin "1") (pinfunction "1_1") (pintype "passive"))
      (node (ref "TP15") (pin "TP") (pinfunction "TP_TP") (pintype "input"))
      (node (ref "U2") (pin "8") (pinfunction "IO0_8") (pintype "bidirectional"))
      (node (ref "U3") (pin "3") (pinfunction "SQW/~{INT}_3") (pintype "output"))
    )
    (net (code "17") (name "IO{slash}BOOT") (class "Default")
      (node (ref "BOOT_BUTTON") (pin "3") (pinfunction "3_3") (pintype "passive"))
      (node (ref "BOOT_BUTTON") (pin "4") (pinfunction "4_4") (pintype "passive"))
      (node (ref "C8") (pin "1") (pinfunction "1_1") (pintype "passive"))
      (node (ref "R_BOOT") (pin "1") (pinfunction "1_1") (pintype "passive"))
      (node (ref "U2") (pin "15") (pinfunction "IO9_15") (pintype "bidirectional"))
    )
    (net (code "18") (name "IO{slash}CHANGE") (class "Default")
      (node (ref "C10") (pin "1") (pinfunction "1_1") (pintype "passive"))
      (node (ref "CHANGE_BUTTON") (pin "3") (pinfunction "3_3") (pintype "passive"))
      (node (ref "CHANGE_BUTTON") (pin "4") (pinfunction "4_4") (pintype "passive"))
      (node (ref "R_CHANGE") (pin "1") (pinfunction "1_1") (pintype "passive"))
      (node (ref "U2") (pin "23") (pinfunction "IO15_23") (pintype "bidirectional"))
    )
    (net (code "19") (name "MISO") (class "Default")
      (node (ref "D12") (pin "2") (pinfunction "2_2") (pintype "passive"))
      (node (ref "J4") (pin "P7") (pinfunction "DAT0_P7") (pintype "bidirectional"))
      (node (ref "R5") (pin "1") (pinfunction "1_1") (pintype "passive"))
      (node (ref "TP6") (pin "TP") (pinfunction "TP_TP") (pintype "input"))
      (node (ref "U2") (pin "27") (pinfunction "IO2_27") (pintype "bidirectional"))
      (node (ref "U5") (pin "2") (pinfunction "DO(IO1)_2") (pintype "bidirectional"))
    )
    (net (code "20") (name "MOSI") (class "Default")
      (node (ref "D11") (pin "2") (pinfunction "2_2") (pintype "passive"))
      (node (ref "J1") (pin "14") (pinfunction "14_14") (pintype "bidirectional"))
      (node (ref "J4") (pin "P3") (pinfunction "CMD_P3") (pintype "bidirectional"))
      (node (ref "R6") (pin "1") (pinfunction "1_1") (pintype "passive"))
      (node (ref "TP7") (pin "TP") (pinfunction "TP_TP") (pintype "input"))
      (node (ref "U2") (pin "7") (pinfunction "IO7_7") (pintype "bidirectional"))
      (node (ref "U5") (pin "5") (pinfunction "DI(IO0)_5") (pintype "bidirectional"))
    )
    (net (code "21") (name "Net-(CHG_LED-PadC)") (class "Default")
      (node (ref "CHG_LED") (pin "C") (pinfunction "C_C") (pintype "passive"))
      (node (ref "R1_BAT") (pin "1") (pinfunction "1_1") (pintype "passive"))
    )
    (net (code "22") (name "Net-(D2-CATHODE)") (class "Default")
      (node (ref "C1_BAT1") (pin "1") (pinfunction "1_1") (pintype "passive"))
      (node (ref "D2") (pin "1") (pinfunction "CATHODE_1") (pintype "bidirectional"))
      (node (ref "IC4") (pin "1") (pinfunction "VIN_1") (pintype "bidirectional"))
      (node (ref "IC4") (pin "3") (pinfunction "CE_3") (pintype "bidirectional"))
      (node (ref "Q1") (pin "2") (pinfunction "S_2") (pintype "bidirectional"))
    )
    (net (code "23") (name "Net-(D7-CATHODE)") (class "Default")
      (node (ref "D7") (pin "1") (pinfunction "CATHODE_1") (pintype "bidirectional"))
      (node (ref "R_CAPACITOR") (pin "1") (pinfunction "1_1") (pintype "passive"))
    )
    (net (code "24") (name "Net-(EPD_C1-Pad1)") (class "Default")
      (node (ref "EPD_C1") (pin "1") (pinfunction "1_1") (pintype "passive"))
      (node (ref "J1") (pin "4") (pinfunction "4_4") (pintype "bidirectional"))
    )
    (net (code "25") (name "Net-(EPD_C2-Pad1)") (class "Default")
      (node (ref "EPD_C2") (pin "1") (pinfunction "1_1") (pintype "passive"))
      (node (ref "J1") (pin "5") (pinfunction "5_5") (pintype "bidirectional"))
    )
    (net (code "26") (name "Net-(EPD_C6-Pad1)") (class "Default")
      (node (ref "EPD_C6") (pin "1") (pinfunction "1_1") (pintype "passive"))
      (node (ref "J1") (pin "18") (pinfunction "18_18") (pintype "bidirectional"))
    )
    (net (code "27") (name "Net-(EPD_C7-Pad1)") (class "Default")
      (node (ref "EPD_C7") (pin "1") (pinfunction "1_1") (pintype "passive"))
      (node (ref "J1") (pin "19") (pinfunction "19_19") (pintype "bidirectional"))
    )
    (net (code "28") (name "Net-(EPD_C8-Pad1)") (class "Default")
      (node (ref "EPD_C8") (pin "1") (pinfunction "1_1") (pintype "passive"))
      (node (ref "J1") (pin "20") (pinfunction "20_20") (pintype "bidirectional"))
    )
    (net (code "29") (name "Net-(EPD_C10-Pad1)") (class "Default")
      (node (ref "EPD_C10") (pin "1") (pinfunction "1_1") (pintype "passive"))
      (node (ref "J1") (pin "22") (pinfunction "22_22") (pintype "bidirectional"))
    )
    (net (code "30") (name "Net-(EPD_C12-Pad1)") (class "Default")
      (node (ref "EPD_C12") (pin "1") (pinfunction "1_1") (pintype "passive"))
      (node (ref "J1") (pin "24") (pinfunction "24_24") (pintype "bidirectional"))
    )
    (net (code "31") (name "Net-(IC1-CT)") (class "Default")
      (node (ref "C_DELAY") (pin "1") (pinfunction "1_1") (pintype "passive"))
      (node (ref "IC1") (pin "5") (pinfunction "CT_5") (pintype "bidirectional"))
    )
    (net (code "32") (name "Net-(J2-PadA5)") (class "Default")
      (node (ref "J2") (pin "A5") (pinfunction "A5_A5") (pintype "bidirectional"))
      (node (ref "R2-USB1") (pin "2") (pinfunction "2_2") (pintype "passive"))
    )
    (net (code "33") (name "Net-(J2-PadB5)") (class "Default")
      (node (ref "J2") (pin "B5") (pinfunction "B5_B5") (pintype "bidirectional"))
      (node (ref "R2-USB") (pin "1") (pinfunction "1_1") (pintype "passive"))
    )
    (net (code "34") (name "Net-(J4-VDD)") (class "Default")
      (node (ref "C9") (pin "1") (pinfunction "1_1") (pintype "passive"))
      (node (ref "J4") (pin "P4") (pinfunction "VDD_P4") (pintype "bidirectional"))
    )
    (net (code "35") (name "Net-(J4-VSS)") (class "Default")
      (node (ref "C9") (pin "2") (pinfunction "2_2") (pintype "passive"))
      (node (ref "J4") (pin "P6") (pinfunction "VSS_P6") (pintype "bidirectional"))
    )
    (net (code "36") (name "Net-(U1-PROG)") (class "Default")
      (node (ref "R2_BAT") (pin "2") (pinfunction "2_2") (pintype "passive"))
      (node (ref "U1") (pin "5") (pinfunction "PROG_5") (pintype "input"))
    )
    (net (code "37") (name "Net-(U1-STAT)") (class "Default")
      (node (ref "R1_BAT") (pin "2") (pinfunction "2_2") (pintype "passive"))
      (node (ref "U1") (pin "1") (pinfunction "STAT_1") (pintype "output"))
    )
    (net (code "38") (name "PREVGH") (class "Default")
      (node (ref "D5") (pin "1") (pinfunction "K_1") (pintype "bidirectional"))
      (node (ref "EPD_C9") (pin "1") (pinfunction "1_1") (pintype "passive"))
      (node (ref "J1") (pin "21") (pinfunction "21_21") (pintype "bidirectional"))
    )
    (net (code "39") (name "PREVGL") (class "Default")
      (node (ref "D4") (pin "2") (pinfunction "A_2") (pintype "bidirectional"))
      (node (ref "EPD_C11") (pin "1") (pinfunction "1_1") (pintype "passive"))
      (node (ref "J1") (pin "23") (pinfunction "23_23") (pintype "bidirectional"))
    )
    (net (code "40") (name "RESE") (class "Default")
      (node (ref "J1") (pin "3") (pinfunction "3_3") (pintype "bidirectional"))
      (node (ref "Q3") (pin "2") (pinfunction "S_2") (pintype "bidirectional"))
      (node (ref "R3") (pin "2") (pinfunction "2_2") (pintype "passive"))
    )
    (net (code "41") (name "RESE'") (class "Default")
      (node (ref "R2") (pin "2") (pinfunction "2_2") (pintype "passive"))
      (node (ref "R3") (pin "1") (pinfunction "1_1") (pintype "passive"))
      (node (ref "SJ1") (pin "2") (pinfunction "2_2") (pintype "passive"))
    )
    (net (code "42") (name "RESET") (class "Default")
      (node (ref "C5") (pin "1") (pinfunction "1_1") (pintype "passive"))
      (node (ref "IC1") (pin "1") (pinfunction "VOUT_1") (pintype "bidirectional"))
      (node (ref "RESET_BUTTON") (pin "3") (pinfunction "3_3") (pintype "passive"))
      (node (ref "RESET_BUTTON") (pin "4") (pinfunction "4_4") (pintype "passive"))
      (node (ref "R_RESET") (pin "1") (pinfunction "1_1") (pintype "passive"))
      (node (ref "U2") (pin "3") (pinfunction "EN_3") (pintype "input"))
    )
    (net (code "43") (name "RTC_RST") (class "Default")
      (node (ref "U2") (pin "16") (pinfunction "IO18_16") (pintype "bidirectional"))
      (node (ref "U3") (pin "4") (pinfunction "~{RST}_4") (pintype "input"))
    )
    (net (code "44") (name "RX") (class "Default")
      (node (ref "TP2") (pin "TP") (pinfunction "TP_TP") (pintype "input"))
      (node (ref "U2") (pin "24") (pinfunction "RXD0/GPIO17_24") (pintype "bidirectional"))
    )
    (net (code "45") (name "SCK") (class "Default")
      (node (ref "D10") (pin "2") (pinfunction "2_2") (pintype "passive"))
      (node (ref "J1") (pin "13") (pinfunction "13_13") (pintype "bidirectional"))
      (node (ref "J4") (pin "P5") (pinfunction "CLK_P5") (pintype "bidirectional"))
      (node (ref "R7") (pin "1") (pinfunction "1_1") (pintype "passive"))
      (node (ref "TP8") (pin "TP") (pinfunction "TP_TP") (pintype "input"))
      (node (ref "U2") (pin "6") (pinfunction "IO6_6") (pintype "bidirectional"))
      (node (ref "U5") (pin "6") (pinfunction "CLK_6") (pintype "input"))
    )
    (net (code "46") (name "SCL") (class "Default")
      (node (ref "J3") (pin "4") (pinfunction "4_4") (pintype "passive"))
      (node (ref "R2_PINH") (pin "1") (pinfunction "1_1") (pintype "passive"))
      (node (ref "SENSOR2") (pin "4") (pinfunction "SCK_4") (pintype "input"))
      (node (ref "U2") (pin "20") (pinfunction "IO22_20") (pintype "bidirectional"))
      (node (ref "U3") (pin "16") (pinfunction "SCL_16") (pintype "input"))
      (node (ref "U4") (pin "7") (pinfunction "SCL_7") (pintype "input"))
    )
    (net (code "47") (name "SDA") (class "Default")
      (node (ref "J3") (pin "3") (pinfunction "3_3") (pintype "passive"))
      (node (ref "R1_PINH") (pin "1") (pinfunction "1_1") (pintype "passive"))
      (node (ref "SENSOR2") (pin "3") (pinfunction "SDI_3") (pintype "bidirectional"))
      (node (ref "U2") (pin "19") (pinfunction "IO21_19") (pintype "bidirectional"))
      (node (ref "U3") (pin "15") (pinfunction "SDA_15") (pintype "bidirectional"))
      (node (ref "U4") (pin "8") (pinfunction "SDA_8") (pintype "bidirectional"))
    )
    (net (code "48") (name "SRC") (class "Default")
      (node (ref "C4") (pin "1") (pinfunction "1_1") (pintype "passive"))
      (node (ref "C4") (pin "2") (pinfunction "2_2") (pintype "passive"))
      (node (ref "D3") (pin "2") (pinfunction "A_2") (pintype "bidirectional"))
      (node (ref "D4") (pin "1") (pinfunction "K_1") (pintype "bidirectional"))
      (node (ref "D5") (pin "2") (pinfunction "A_2") (pintype "bidirectional"))
      (node (ref "L1") (pin "1") (pinfunction "1_1") (pintype "passive"))
      (node (ref "Q3") (pin "3") (pinfunction "D_3") (pintype "bidirectional"))
    )
    (net (code "49") (name "SS_SD") (class "Default")
      (node (ref "D6") (pin "2") (pinfunction "2_2") (pintype "passive"))
      (node (ref "J4") (pin "P2") (pinfunction "CD/DAT3_P2") (pintype "bidirectional"))
      (node (ref "R10") (pin "1") (pinfunction "1_1") (pintype "passive"))
      (node (ref "U2") (pin "4") (pinfunction "IO4_4") (pintype "bidirectional"))
    )
    (net (code "50") (name "TX") (class "Default")
      (node (ref "TP1") (pin "TP") (pinfunction "TP_TP") (pintype "input"))
      (node (ref "U2") (pin "25") (pinfunction "TXD0/GPIO16_25") (pintype "bidirectional"))
    )
    (net (code "51") (name "USB_D+") (class "Default")
      (node (ref "D1") (pin "1") (pinfunction "I/O1_1_1") (pintype "bidirectional"))
      (node (ref "U2") (pin "14") (pinfunction "IO13_14") (pintype "bidirectional"))
    )
    (net (code "52") (name "USB_D-") (class "Default")
      (node (ref "D1") (pin "3") (pinfunction "I/O2_1_3") (pintype "bidirectional"))
      (node (ref "U2") (pin "13") (pinfunction "IO12_13") (pintype "bidirectional"))
    )
    (net (code "53") (name "VBAT") (class "Default")
      (node (ref "C2_BAT") (pin "1") (pinfunction "1_1") (pintype "passive"))
      (node (ref "Q1") (pin "3") (pinfunction "D_3") (pintype "bidirectional"))
      (node (ref "TP3") (pin "TP") (pinfunction "TP_TP") (pintype "input"))
      (node (ref "U1") (pin "3") (pinfunction "VBAT_3") (pintype "power_in"))
      (node (ref "U4") (pin "2") (pinfunction "CELL_2") (pintype "power_in"))
      (node (ref "U4") (pin "3") (pinfunction "VDD_3") (pintype "power_in"))
    )
    (net (code "54") (name "VBUS") (class "Default")
      (node (ref "C1_BAT") (pin "1") (pinfunction "1_1") (pintype "passive"))
      (node (ref "C4_USB") (pin "1") (pinfunction "1_1") (pintype "passive"))
      (node (ref "C5_USB") (pin "1") (pinfunction "1_1") (pintype "passive"))
      (node (ref "CHG_LED") (pin "A") (pinfunction "A_A") (pintype "passive"))
      (node (ref "D1") (pin "5") (pinfunction "VBUS_5") (pintype "bidirectional"))
      (node (ref "D2") (pin "2") (pinfunction "ANODE_2") (pintype "bidirectional"))
      (node (ref "PFMF.050.1") (pin "2") (pinfunction "2_2") (pintype "passive"))
      (node (ref "Q1") (pin "1") (pinfunction "G_1") (pintype "bidirectional"))
      (node (ref "R1_PWRBUS") (pin "2") (pinfunction "2_2") (pintype "passive"))
      (node (ref "TP14") (pin "TP") (pinfunction "TP_TP") (pintype "input"))
      (node (ref "U1") (pin "4") (pinfunction "VIN_4") (pintype "power_in"))
    )
    (net (code "55") (name "VRTC") (class "Default")
      (node (ref "C10_SUPERCAP") (pin "2") (pinfunction "2_2") (pintype "passive"))
      (node (ref "C11") (pin "1") (pinfunction "1_1") (pintype "passive"))
      (node (ref "R_CAPACITOR") (pin "2") (pinfunction "2_2") (pintype "passive"))
      (node (ref "U3") (pin "14") (pinfunction "VBAT_14") (pintype "power_in"))
    )
    (net (code "56") (name "VUSB") (class "Default")
      (node (ref "J2") (pin "A4") (pinfunction "A4_A4") (pintype "bidirectional"))
      (node (ref "J2") (pin "A9") (pinfunction "A9_A9") (pintype "bidirectional"))
      (node (ref "J2") (pin "B4") (pinfunction "B4_B4") (pintype "bidirectional"))
      (node (ref "J2") (pin "B9") (pinfunction "B9_B9") (pintype "bidirectional"))
      (node (ref "PFMF.050.1") (pin "1") (pinfunction "1_1") (pintype "passive"))
    )
    (net (code "57") (name "unconnected-(IC1-NC-Pad4)") (class "Default")
      (node (ref "IC1") (pin "4") (pinfunction "NC_4") (pintype "no_connect"))
    )
    (net (code "58") (name "unconnected-(IC4-NC-Pad4)") (class "Default")
      (node (ref "IC4") (pin "4") (pinfunction "NC_4") (pintype "no_connect"))
    )
    (net (code "59") (name "unconnected-(J1-Pad1)") (class "Default")
      (node (ref "J1") (pin "1") (pinfunction "1_1") (pintype "bidirectional"))
    )
    (net (code "60") (name "unconnected-(J1-Pad6)") (class "Default")
      (node (ref "J1") (pin "6") (pinfunction "6_6") (pintype "bidirectional"))
    )
    (net (code "61") (name "unconnected-(J1-Pad7)") (class "Default")
      (node (ref "J1") (pin "7") (pinfunction "7_7") (pintype "bidirectional"))
    )
    (net (code "62") (name "unconnected-(J2-PadA8)") (class "Default")
      (node (ref "J2") (pin "A8") (pinfunction "A8_A8") (pintype "bidirectional"))
    )
    (net (code "63") (name "unconnected-(J2-PadB8)") (class "Default")
      (node (ref "J2") (pin "B8") (pinfunction "B8_B8") (pintype "bidirectional"))
    )
    (net (code "64") (name "unconnected-(J4-DAT1-PadP8)") (class "Default")
      (node (ref "J4") (pin "P8") (pinfunction "DAT1_P8") (pintype "bidirectional"))
    )
    (net (code "65") (name "unconnected-(J4-DAT2-PadP1)") (class "Default")
      (node (ref "J4") (pin "P1") (pinfunction "DAT2_P1") (pintype "bidirectional"))
    )
    (net (code "66") (name "unconnected-(J4-DETECTION_1-PadS1)") (class "Default")
      (node (ref "J4") (pin "S1") (pinfunction "DETECTION_1_S1") (pintype "bidirectional"))
    )
    (net (code "67") (name "unconnected-(J4-DETECTION_2-PadS2)") (class "Default")
      (node (ref "J4") (pin "S2") (pinfunction "DETECTION_2_S2") (pintype "bidirectional"))
    )
    (net (code "68") (name "unconnected-(U2-NC-Pad22)") (class "Default")
      (node (ref "U2") (pin "22") (pinfunction "NC_22") (pintype "no_connect"))
    )
    (net (code "69") (name "unconnected-(U4-~{ALERT}-Pad5)") (class "Default")
      (node (ref "U4") (pin "5") (pinfunction "~{ALERT}_5") (pintype "output"))
    )
  )
)
